# 3PDT.net
KiCad netlist of a schematic drawn in Altium Designer
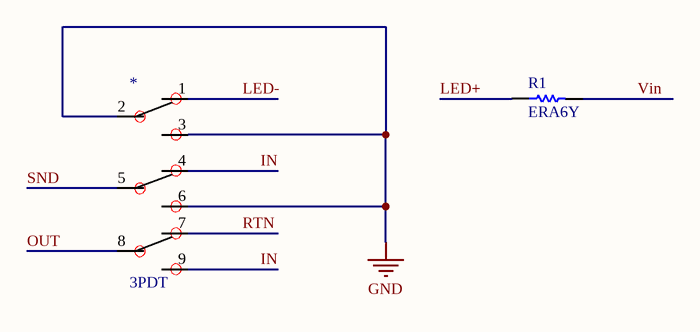
[diagram p0: 3PDT.SchDoc]

(export (version "E")
  (design (tool "Eeschema 10.0.6"))
  (components
    (comp (ref "*") (value "3PDT") (footprint "3PDT") (libsource (lib "Parts") (part "3PDT")))
    (comp (ref "R1")
      (value "ERA6Y")
      (footprint "ERA-0805")
      (fields (field (name "PUBLISHER") "Altium Limited"))
      (libsource (lib "Panasonic Resistor") (part "ERA6Y"))
    )
  )
  (nets
    (net (code "1") (name "/IN") (class "Default")
      (node (ref "*") (pin "4") (pinfunction "2_4") (pintype "passive"))
      (node (ref "*") (pin "9") (pinfunction "9_9") (pintype "passive"))
    )
    (net (code "2") (name "/LED+") (class "Default")
      (node (ref "R1") (pin "1") (pinfunction "1_1") (pintype "passive"))
    )
    (net (code "3") (name "/LED-") (class "Default")
      (node (ref "*") (pin "1") (pinfunction "1_1") (pintype "passive"))
    )
    (net (code "4") (name "/OUT") (class "Default")
      (node (ref "*") (pin "8") (pinfunction "8_8") (pintype "passive"))
    )
    (net (code "5") (name "/RTN") (class "Default")
      (node (ref "*") (pin "7") (pinfunction "7_7") (pintype "passive"))
    )
    (net (code "6") (name "/SND") (class "Default")
      (node (ref "*") (pin "5") (pinfunction "5_5") (pintype "passive"))
    )
    (net (code "7") (name "/Vin") (class "Default")
      (node (ref "R1") (pin "2") (pinfunction "2_2") (pintype "passive"))
    )
    (net (code "8") (name "GND") (class "Default")
      (node (ref "*") (pin "2") (pinfunction "4_2") (pintype "passive"))
      (node (ref "*") (pin "3") (pinfunction "3_3") (pintype "passive"))
      (node (ref "*") (pin "6") (pinfunction "8_6") (pintype "passive"))
    )
  )
)
